# proj_arhipov_uart_rs232.net
KiCad netlist of a schematic drawn in Altium Designer
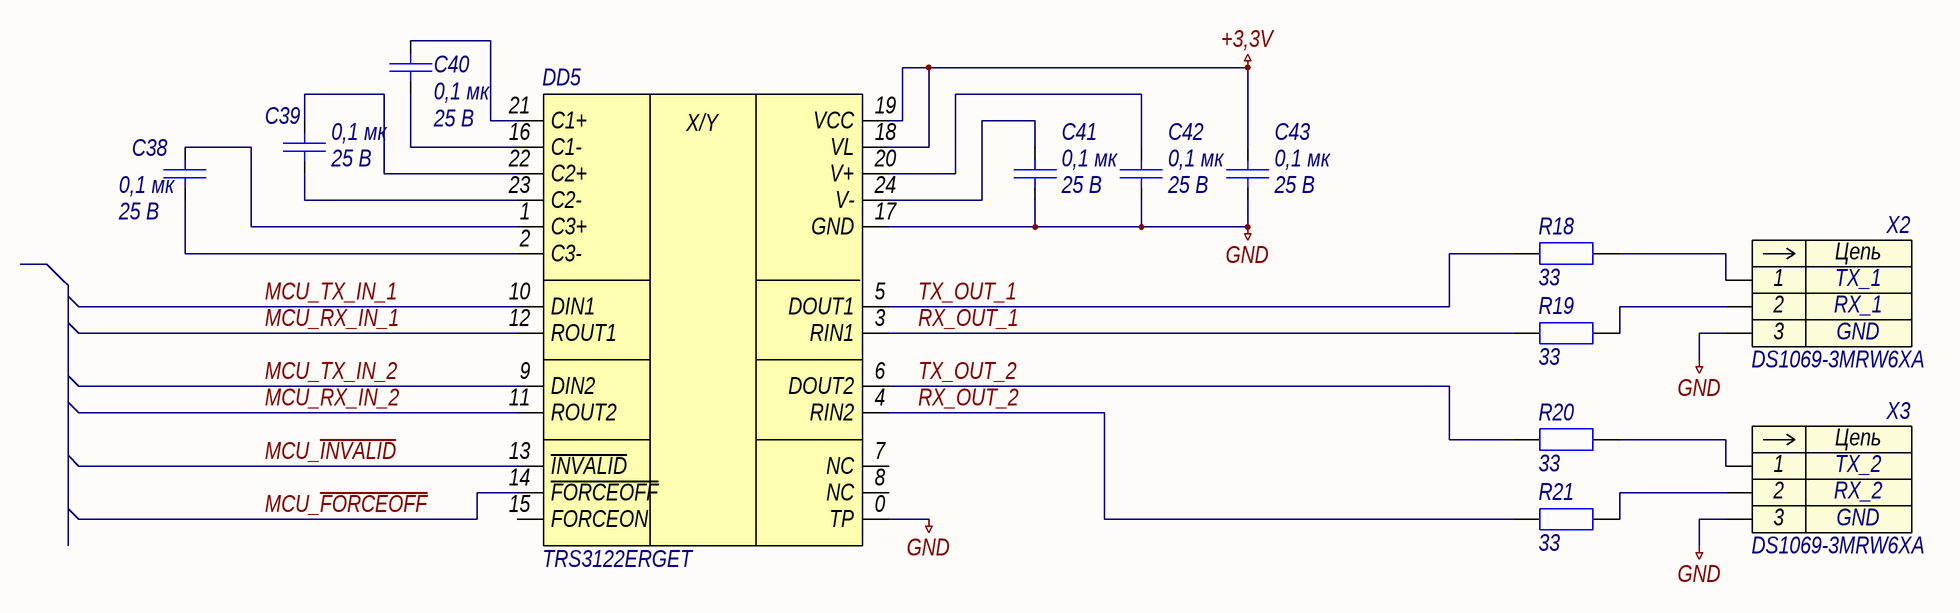
[diagram p0: proj_arhipov_uart_rs232.SchDoc]

(export (version "E")
  (design (tool "Eeschema 10.0.6"))
  (components
    (comp (ref "C38")
      (value "0,1 мк")
      (footprint "C0603")
      (description "=Описание")
      (fields (field (name "НАПРЯЖЕНИЕ") "25 В"))
      (libsource (lib "Database_Students") (part "CAPACITOR-NONPOLAR"))
    )
    (comp (ref "C39")
      (value "0,1 мк")
      (footprint "C0603")
      (description "=Описание")
      (fields (field (name "НАПРЯЖЕНИЕ") "25 В"))
      (libsource (lib "Database_Students") (part "CAPACITOR-NONPOLAR"))
    )
    (comp (ref "C40")
      (value "0,1 мк")
      (footprint "C0603")
      (description "=Описание")
      (fields (field (name "НАПРЯЖЕНИЕ") "25 В"))
      (libsource (lib "Database_Students") (part "CAPACITOR-NONPOLAR"))
    )
    (comp (ref "C41")
      (value "0,1 мк")
      (footprint "C0603")
      (description "=Описание")
      (fields (field (name "НАПРЯЖЕНИЕ") "25 В"))
      (libsource (lib "Database_Students") (part "CAPACITOR-NONPOLAR"))
    )
    (comp (ref "C42")
      (value "0,1 мк")
      (footprint "C0603")
      (description "=Описание")
      (fields (field (name "НАПРЯЖЕНИЕ") "25 В"))
      (libsource (lib "Database_Students") (part "CAPACITOR-NONPOLAR"))
    )
    (comp (ref "C43")
      (value "0,1 мк")
      (footprint "C0603")
      (description "=Описание")
      (fields (field (name "НАПРЯЖЕНИЕ") "25 В"))
      (libsource (lib "Database_Students") (part "CAPACITOR-NONPOLAR"))
    )
    (comp (ref "DD5")
      (value "TRS3122ERGET")
      (footprint "QFN-24-400X400X80")
      (description "=Описание")
      (libsource (lib "Database_Students") (part "TRS3122ERGET"))
    )
    (comp (ref "R18")
      (value "33")
      (footprint "R0603")
      (description "=Описание")
      (libsource (lib "Database_Students") (part "R-0.05W"))
    )
    (comp (ref "R19")
      (value "33")
      (footprint "R0603")
      (description "=Описание")
      (libsource (lib "Database_Students") (part "R-0.05W"))
    )
    (comp (ref "R20")
      (value "33")
      (footprint "R0603")
      (description "=Описание")
      (libsource (lib "Database_Students") (part "R-0.05W"))
    )
    (comp (ref "R21")
      (value "33")
      (footprint "R0603")
      (description "=Описание")
      (libsource (lib "Database_Students") (part "R-0.05W"))
    )
    (comp (ref "X2")
      (value "DS1069-3MRW6XA")
      (footprint "DS1069-3MRW6XA")
      (description "=Описание")
      (libsource (lib "Database_Students") (part "HEADER-3-PLG"))
    )
    (comp (ref "X3")
      (value "DS1069-3MRW6XA")
      (footprint "DS1069-3MRW6XA")
      (description "=Описание")
      (libsource (lib "Database_Students") (part "HEADER-3-PLG"))
    )
  )
  (nets
    (net (code "1") (name "+3,3V") (class "Default")
      (node (ref "C43") (pin "2") (pinfunction "2_2") (pintype "passive"))
      (node (ref "DD5") (pin "18") (pinfunction "VL_18") (pintype "passive"))
      (node (ref "DD5") (pin "19") (pinfunction "VCC_19") (pintype "passive"))
    )
    (net (code "2") (name "/MCU_RX_IN_1") (class "Default")
      (node (ref "DD5") (pin "12") (pinfunction "ROUT1_12") (pintype "passive"))
    )
    (net (code "3") (name "/MCU_RX_IN_2") (class "Default")
      (node (ref "DD5") (pin "11") (pinfunction "ROUT2_11") (pintype "passive"))
    )
    (net (code "4") (name "/MCU_TX_IN_1") (class "Default")
      (node (ref "DD5") (pin "10") (pinfunction "DIN1_10") (pintype "passive"))
    )
    (net (code "5") (name "/MCU_TX_IN_2") (class "Default")
      (node (ref "DD5") (pin "9") (pinfunction "DIN2_9") (pintype "passive"))
    )
    (net (code "6") (name "/MCU_~{FORCEOFF}") (class "Default")
      (node (ref "DD5") (pin "14") (pinfunction "~{FORCEOFF}_14") (pintype "passive"))
    )
    (net (code "7") (name "/MCU_~{INVALID}") (class "Default")
      (node (ref "DD5") (pin "13") (pinfunction "~{INVALID}_13") (pintype "passive"))
    )
    (net (code "8") (name "/RX_OUT_1") (class "Default")
      (node (ref "DD5") (pin "3") (pinfunction "RIN1_3") (pintype "passive"))
      (node (ref "R19") (pin "1") (pinfunction "1_1") (pintype "passive"))
    )
    (net (code "9") (name "/RX_OUT_2") (class "Default")
      (node (ref "DD5") (pin "4") (pinfunction "RIN2_4") (pintype "passive"))
      (node (ref "R21") (pin "1") (pinfunction "1_1") (pintype "passive"))
    )
    (net (code "10") (name "/TX_OUT_1") (class "Default")
      (node (ref "DD5") (pin "5") (pinfunction "DOUT1_5") (pintype "passive"))
      (node (ref "R18") (pin "1") (pinfunction "1_1") (pintype "passive"))
    )
    (net (code "11") (name "/TX_OUT_2") (class "Default")
      (node (ref "DD5") (pin "6") (pinfunction "DOUT2_6") (pintype "passive"))
      (node (ref "R20") (pin "1") (pinfunction "1_1") (pintype "passive"))
    )
    (net (code "12") (name "GND") (class "Default")
      (node (ref "C41") (pin "1") (pinfunction "1_1") (pintype "passive"))
      (node (ref "C42") (pin "1") (pinfunction "1_1") (pintype "passive"))
      (node (ref "C43") (pin "1") (pinfunction "1_1") (pintype "passive"))
      (node (ref "DD5") (pin "0") (pinfunction "TP_0") (pintype "passive"))
      (node (ref "DD5") (pin "17") (pinfunction "GND_17") (pintype "passive"))
      (node (ref "X2") (pin "3") (pinfunction "3_3") (pintype "passive"))
      (node (ref "X3") (pin "3") (pinfunction "3_3") (pintype "passive"))
    )
    (net (code "13") (name "Net-(DD5-C1+)") (class "Default")
      (node (ref "C40") (pin "1") (pinfunction "1_1") (pintype "passive"))
      (node (ref "DD5") (pin "21") (pinfunction "C1+_21") (pintype "passive"))
    )
    (net (code "14") (name "Net-(DD5-C1-)") (class "Default")
      (node (ref "C40") (pin "2") (pinfunction "2_2") (pintype "passive"))
      (node (ref "DD5") (pin "16") (pinfunction "C1-_16") (pintype "passive"))
    )
    (net (code "15") (name "Net-(DD5-C2+)") (class "Default")
      (node (ref "C39") (pin "2") (pinfunction "2_2") (pintype "passive"))
      (node (ref "DD5") (pin "22") (pinfunction "C2+_22") (pintype "passive"))
    )
    (net (code "16") (name "Net-(DD5-C2-)") (class "Default")
      (node (ref "C39") (pin "1") (pinfunction "1_1") (pintype "passive"))
      (node (ref "DD5") (pin "23") (pinfunction "C2-_23") (pintype "passive"))
    )
    (net (code "17") (name "Net-(DD5-C3+)") (class "Default")
      (node (ref "C38") (pin "2") (pinfunction "2_2") (pintype "passive"))
      (node (ref "DD5") (pin "1") (pinfunction "C3+_1") (pintype "passive"))
    )
    (net (code "18") (name "Net-(DD5-C3-)") (class "Default")
      (node (ref "C38") (pin "1") (pinfunction "1_1") (pintype "passive"))
      (node (ref "DD5") (pin "2") (pinfunction "C3-_2") (pintype "passive"))
    )
    (net (code "19") (name "Net-(DD5-V+)") (class "Default")
      (node (ref "C42") (pin "2") (pinfunction "2_2") (pintype "passive"))
      (node (ref "DD5") (pin "20") (pinfunction "V+_20") (pintype "passive"))
    )
    (net (code "20") (name "Net-(DD5-V-)") (class "Default")
      (node (ref "C41") (pin "2") (pinfunction "2_2") (pintype "passive"))
      (node (ref "DD5") (pin "24") (pinfunction "V-_24") (pintype "passive"))
    )
    (net (code "21") (name "Net-(R18-Pad2)") (class "Default")
      (node (ref "R18") (pin "2") (pinfunction "2_2") (pintype "passive"))
      (node (ref "X2") (pin "1") (pinfunction "1_1") (pintype "passive"))
    )
    (net (code "22") (name "Net-(R19-Pad2)") (class "Default")
      (node (ref "R19") (pin "2") (pinfunction "2_2") (pintype "passive"))
      (node (ref "X2") (pin "2") (pinfunction "2_2") (pintype "passive"))
    )
    (net (code "23") (name "Net-(R20-Pad2)") (class "Default")
      (node (ref "R20") (pin "2") (pinfunction "2_2") (pintype "passive"))
      (node (ref "X3") (pin "1") (pinfunction "1_1") (pintype "passive"))
    )
    (net (code "24") (name "Net-(R21-Pad2)") (class "Default")
      (node (ref "R21") (pin "2") (pinfunction "2_2") (pintype "passive"))
      (node (ref "X3") (pin "2") (pinfunction "2_2") (pintype "passive"))
    )
    (net (code "25") (name "unconnected-(DD5-FORCEON-Pad15)") (class "Default")
      (node (ref "DD5") (pin "15") (pinfunction "FORCEON_15") (pintype "passive"))
    )
    (net (code "26") (name "unconnected-(DD5-NC-Pad7)") (class "Default")
      (node (ref "DD5") (pin "7") (pinfunction "NC_7") (pintype "passive"))
    )
    (net (code "27") (name "unconnected-(DD5-NC-Pad8)") (class "Default")
      (node (ref "DD5") (pin "8") (pinfunction "NC_8") (pintype "passive"))
    )
  )
)
